# sticky-watch-v1_5.net
KiCad netlist of a schematic drawn in EAGLE
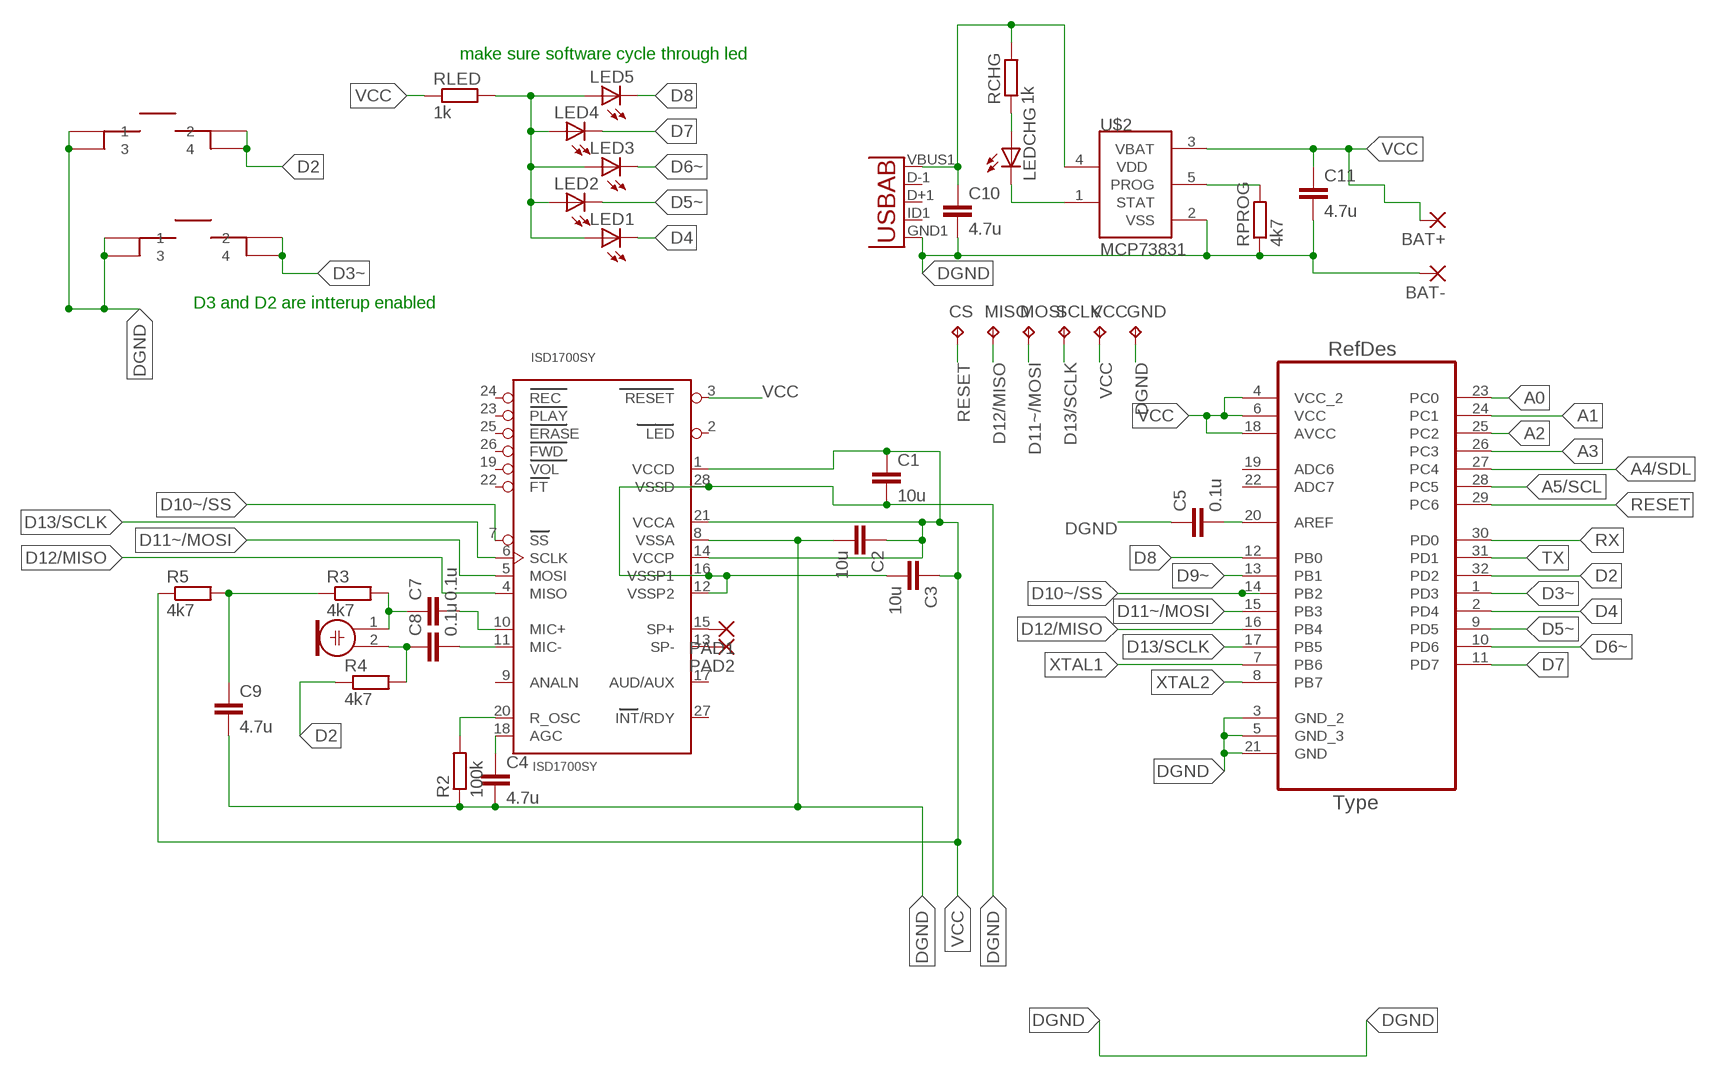
[diagram p0: schematic, sheet 1]

(export (version "E")
  (design (tool "Eeschema 10.0.6"))
  (components
    (comp (ref "BAT+")
      (value "1,6/0,8")
      (footprint "eagle-import:1,6_0,8")
      (libsource (lib "eagle-import") (part "1,6/0,8"))
    )
    (comp (ref "BAT-")
      (value "1,6/0,8")
      (footprint "eagle-import:1,6_0,8")
      (libsource (lib "eagle-import") (part "1,6/0,8"))
    )
    (comp (ref "C1")
      (value "10u")
      (footprint "eagle-import:C0603")
      (libsource (lib "eagle-import") (part "C-EUC0603"))
    )
    (comp (ref "C2")
      (value "10u")
      (footprint "eagle-import:C0603")
      (libsource (lib "eagle-import") (part "C-EUC0603"))
    )
    (comp (ref "C3")
      (value "10u")
      (footprint "eagle-import:C0603")
      (libsource (lib "eagle-import") (part "C-EUC0603"))
    )
    (comp (ref "C4")
      (value "4.7u")
      (footprint "eagle-import:C0603")
      (libsource (lib "eagle-import") (part "C-EUC0603"))
    )
    (comp (ref "C5")
      (value "0.1u")
      (footprint "eagle-import:C0603")
      (libsource (lib "eagle-import") (part "C-EUC0603"))
    )
    (comp (ref "C7")
      (value "0.1u")
      (footprint "eagle-import:C0603")
      (libsource (lib "eagle-import") (part "C-EUC0603"))
    )
    (comp (ref "C8")
      (value "0.1u")
      (footprint "eagle-import:C0603")
      (libsource (lib "eagle-import") (part "C-EUC0603"))
    )
    (comp (ref "C9")
      (value "4.7u")
      (footprint "eagle-import:C0603")
      (libsource (lib "eagle-import") (part "C-EUC0603"))
    )
    (comp (ref "C10")
      (value "4.7u")
      (footprint "eagle-import:C0603")
      (libsource (lib "eagle-import") (part "C-EUC0603"))
    )
    (comp (ref "C11")
      (value "4.7u")
      (footprint "eagle-import:C0603")
      (libsource (lib "eagle-import") (part "C-EUC0603"))
    )
    (comp (ref "CS")
      (value "TPTP10R")
      (footprint "eagle-import:TP10R")
      (libsource (lib "eagle-import") (part "TPTP10R"))
    )
    (comp (ref "GND")
      (value "TPTP10R")
      (footprint "eagle-import:TP10R")
      (libsource (lib "eagle-import") (part "TPTP10R"))
    )
    (comp (ref "ISD1700SY")
      (value "ISD1700SY")
      (footprint "eagle-import:SO28W")
      (libsource (lib "eagle-import") (part "ISD1700SY"))
    )
    (comp (ref "LED1")
      (value "LEDSML0805")
      (footprint "eagle-import:SML0805")
      (libsource (lib "eagle-import") (part "LEDSML0805"))
    )
    (comp (ref "LED2")
      (value "LEDSML0805")
      (footprint "eagle-import:SML0805")
      (libsource (lib "eagle-import") (part "LEDSML0805"))
    )
    (comp (ref "LED3")
      (value "LEDSML0805")
      (footprint "eagle-import:SML0805")
      (libsource (lib "eagle-import") (part "LEDSML0805"))
    )
    (comp (ref "LED4")
      (value "LEDSML0805")
      (footprint "eagle-import:SML0805")
      (libsource (lib "eagle-import") (part "LEDSML0805"))
    )
    (comp (ref "LED5")
      (value "LEDSML0805")
      (footprint "eagle-import:SML0805")
      (libsource (lib "eagle-import") (part "LEDSML0805"))
    )
    (comp (ref "LEDCHG")
      (value "LEDSML0805")
      (footprint "eagle-import:SML0805")
      (libsource (lib "eagle-import") (part "LEDSML0805"))
    )
    (comp (ref "M1")
      (value "ELECTRET_MICROPHON-WM-63PR")
      (footprint "eagle-import:WM-63PR")
      (libsource (lib "eagle-import") (part "ELECTRET_MICROPHON-WM-63PR"))
    )
    (comp (ref "MISO")
      (value "TPTP10R")
      (footprint "eagle-import:TP10R")
      (libsource (lib "eagle-import") (part "TPTP10R"))
    )
    (comp (ref "MOSI")
      (value "TPTP10R")
      (footprint "eagle-import:TP10R")
      (libsource (lib "eagle-import") (part "TPTP10R"))
    )
    (comp (ref "PAD1")
      (value "1,6/0,8")
      (footprint "eagle-import:1,6_0,8")
      (libsource (lib "eagle-import") (part "1,6/0,8"))
    )
    (comp (ref "PAD2")
      (value "1,6/0,8")
      (footprint "eagle-import:1,6_0,8")
      (libsource (lib "eagle-import") (part "1,6/0,8"))
    )
    (comp (ref "R2")
      (value "100k")
      (footprint "eagle-import:R0603")
      (libsource (lib "eagle-import") (part "R-EU_R0603"))
    )
    (comp (ref "R3")
      (value "4k7")
      (footprint "eagle-import:R0603")
      (libsource (lib "eagle-import") (part "R-EU_R0603"))
    )
    (comp (ref "R4")
      (value "4k7")
      (footprint "eagle-import:R0603")
      (libsource (lib "eagle-import") (part "R-EU_R0603"))
    )
    (comp (ref "R5")
      (value "4k7")
      (footprint "eagle-import:R0603")
      (libsource (lib "eagle-import") (part "R-EU_R0603"))
    )
    (comp (ref "RCHG")
      (value "1k")
      (footprint "eagle-import:R0603")
      (libsource (lib "eagle-import") (part "R-EU_R0603"))
    )
    (comp (ref "RLED")
      (value "1k")
      (footprint "eagle-import:R0603")
      (libsource (lib "eagle-import") (part "R-EU_R0603"))
    )
    (comp (ref "RPROG")
      (value "4k7")
      (footprint "eagle-import:R0603")
      (libsource (lib "eagle-import") (part "R-EU_R0603"))
    )
    (comp (ref "S1")
      (value "0")
      (footprint "eagle-import:SMD-TACT-5.2MM")
      (libsource (lib "eagle-import") (part "SMD-TACT"))
    )
    (comp (ref "S2")
      (value "SMD-TACT")
      (footprint "eagle-import:SMD-TACT-5.2MM")
      (libsource (lib "eagle-import") (part "SMD-TACT"))
    )
    (comp (ref "SCLK")
      (value "TPTP10R")
      (footprint "eagle-import:TP10R")
      (libsource (lib "eagle-import") (part "TPTP10R"))
    )
    (comp (ref "U$2")
      (value "MCP73831")
      (footprint "eagle-import:SOT23-5L")
      (libsource (lib "eagle-import") (part "MCP73831"))
    )
    (comp (ref "U1")
      (value "ATMEGA328P-AU")
      (footprint "eagle-import:QFP80P900X900X120-32N")
      (libsource (lib "eagle-import") (part "ATMEGA328P-AU"))
    )
    (comp (ref "U2")
      (value "USB\"\"")
      (footprint "eagle-import:USB-MICRO-SMD")
      (libsource (lib "eagle-import") (part "USB{dblquote}{dblquote}"))
    )
    (comp (ref "VCC")
      (value "TPTP10R")
      (footprint "eagle-import:TP10R")
      (libsource (lib "eagle-import") (part "TPTP10R"))
    )
  )
  (nets
    (net (code "1") (name "/D3~{}") (class "Default")
      (node (ref "S1") (pin "2") (pinfunction "2_2") (pintype "bidirectional"))
      (node (ref "S1") (pin "4") (pinfunction "4_4") (pintype "bidirectional"))
      (node (ref "U1") (pin "1") (pinfunction "PD3_1") (pintype "bidirectional"))
    )
    (net (code "2") (name "/D5~{}") (class "Default")
      (node (ref "LED2") (pin "C") (pinfunction "C_C") (pintype "passive"))
      (node (ref "U1") (pin "9") (pinfunction "PD5_9") (pintype "bidirectional"))
    )
    (net (code "3") (name "/D6~{}") (class "Default")
      (node (ref "LED3") (pin "C") (pinfunction "C_C") (pintype "passive"))
      (node (ref "U1") (pin "10") (pinfunction "PD6_10") (pintype "bidirectional"))
    )
    (net (code "4") (name "/D9~{}") (class "Default")
      (node (ref "U1") (pin "13") (pinfunction "PB1_13") (pintype "bidirectional"))
    )
    (net (code "5") (name "/D10~{{slash}SS}") (class "Default")
      (node (ref "ISD1700SY") (pin "7") (pinfunction "SS_7") (pintype "input"))
      (node (ref "U1") (pin "14") (pinfunction "PB2_14") (pintype "bidirectional"))
    )
    (net (code "6") (name "/D11~{{slash}MOSI}") (class "Default")
      (node (ref "ISD1700SY") (pin "5") (pinfunction "MOSI_5") (pintype "input"))
      (node (ref "MOSI") (pin "TP") (pinfunction "TP_TP") (pintype "input"))
      (node (ref "U1") (pin "15") (pinfunction "PB3_15") (pintype "bidirectional"))
    )
    (net (code "7") (name "A0") (class "Default")
      (node (ref "U1") (pin "23") (pinfunction "PC0_23") (pintype "bidirectional"))
    )
    (net (code "8") (name "A1") (class "Default")
      (node (ref "U1") (pin "24") (pinfunction "PC1_24") (pintype "bidirectional"))
    )
    (net (code "9") (name "A2") (class "Default")
      (node (ref "U1") (pin "25") (pinfunction "PC2_25") (pintype "bidirectional"))
    )
    (net (code "10") (name "A3") (class "Default")
      (node (ref "U1") (pin "26") (pinfunction "PC3_26") (pintype "bidirectional"))
    )
    (net (code "11") (name "A4{slash}SDL") (class "Default")
      (node (ref "U1") (pin "27") (pinfunction "PC4_27") (pintype "bidirectional"))
    )
    (net (code "12") (name "A5{slash}SCL") (class "Default")
      (node (ref "U1") (pin "28") (pinfunction "PC5_28") (pintype "bidirectional"))
    )
    (net (code "13") (name "D2") (class "Default")
      (node (ref "R4") (pin "1") (pinfunction "1_1") (pintype "passive"))
      (node (ref "S2") (pin "2") (pinfunction "2_2") (pintype "bidirectional"))
      (node (ref "S2") (pin "4") (pinfunction "4_4") (pintype "bidirectional"))
      (node (ref "U1") (pin "32") (pinfunction "PD2_32") (pintype "bidirectional"))
    )
    (net (code "14") (name "D4") (class "Default")
      (node (ref "LED1") (pin "C") (pinfunction "C_C") (pintype "passive"))
      (node (ref "U1") (pin "2") (pinfunction "PD4_2") (pintype "bidirectional"))
    )
    (net (code "15") (name "D7") (class "Default")
      (node (ref "LED4") (pin "C") (pinfunction "C_C") (pintype "passive"))
      (node (ref "U1") (pin "11") (pinfunction "PD7_11") (pintype "bidirectional"))
    )
    (net (code "16") (name "D8") (class "Default")
      (node (ref "LED5") (pin "C") (pinfunction "C_C") (pintype "passive"))
      (node (ref "U1") (pin "12") (pinfunction "PB0_12") (pintype "bidirectional"))
    )
    (net (code "17") (name "D12{slash}MISO") (class "Default")
      (node (ref "ISD1700SY") (pin "4") (pinfunction "MISO_4") (pintype "input"))
      (node (ref "MISO") (pin "TP") (pinfunction "TP_TP") (pintype "input"))
      (node (ref "U1") (pin "16") (pinfunction "PB4_16") (pintype "bidirectional"))
    )
    (net (code "18") (name "D13{slash}SCLK") (class "Default")
      (node (ref "ISD1700SY") (pin "6") (pinfunction "SCLK_6") (pintype "input"))
      (node (ref "SCLK") (pin "TP") (pinfunction "TP_TP") (pintype "input"))
      (node (ref "U1") (pin "17") (pinfunction "PB5_17") (pintype "bidirectional"))
    )
    (net (code "19") (name "DGND") (class "Default")
      (node (ref "BAT-") (pin "1") (pinfunction "P_1") (pintype "passive"))
      (node (ref "C1") (pin "2") (pinfunction "2_2") (pintype "passive"))
      (node (ref "C10") (pin "2") (pinfunction "2_2") (pintype "passive"))
      (node (ref "C11") (pin "2") (pinfunction "2_2") (pintype "passive"))
      (node (ref "C2") (pin "2") (pinfunction "2_2") (pintype "passive"))
      (node (ref "C3") (pin "2") (pinfunction "2_2") (pintype "passive"))
      (node (ref "C4") (pin "2") (pinfunction "2_2") (pintype "passive"))
      (node (ref "C5") (pin "1") (pinfunction "1_1") (pintype "passive"))
      (node (ref "C9") (pin "2") (pinfunction "2_2") (pintype "passive"))
      (node (ref "GND") (pin "TP") (pinfunction "TP_TP") (pintype "input"))
      (node (ref "ISD1700SY") (pin "12") (pinfunction "VSSP2_12") (pintype "power_in"))
      (node (ref "ISD1700SY") (pin "16") (pinfunction "VSSP1_16") (pintype "power_in"))
      (node (ref "ISD1700SY") (pin "28") (pinfunction "VSSD_28") (pintype "power_in"))
      (node (ref "ISD1700SY") (pin "8") (pinfunction "VSSA_8") (pintype "power_in"))
      (node (ref "R2") (pin "1") (pinfunction "1_1") (pintype "passive"))
      (node (ref "RPROG") (pin "1") (pinfunction "1_1") (pintype "passive"))
      (node (ref "S1") (pin "1") (pinfunction "1_1") (pintype "bidirectional"))
      (node (ref "S1") (pin "3") (pinfunction "3_3") (pintype "bidirectional"))
      (node (ref "S2") (pin "1") (pinfunction "1_1") (pintype "bidirectional"))
      (node (ref "S2") (pin "3") (pinfunction "3_3") (pintype "bidirectional"))
      (node (ref "U$2") (pin "2") (pinfunction "VSS_2") (pintype "bidirectional"))
      (node (ref "U1") (pin "21") (pinfunction "GND_21") (pintype "passive"))
      (node (ref "U1") (pin "3") (pinfunction "GND_2_3") (pintype "passive"))
      (node (ref "U1") (pin "5") (pinfunction "GND_3_5") (pintype "passive"))
      (node (ref "U2") (pin "GND1") (pinfunction "GND_GND1") (pintype "bidirectional"))
    )
    (net (code "20") (name "Net-(C7-Pad1)") (class "Default")
      (node (ref "C7") (pin "1") (pinfunction "1_1") (pintype "passive"))
      (node (ref "M1") (pin "1") (pinfunction "1_1") (pintype "passive"))
      (node (ref "R3") (pin "2") (pinfunction "2_2") (pintype "passive"))
    )
    (net (code "21") (name "Net-(C8-Pad1)") (class "Default")
      (node (ref "C8") (pin "1") (pinfunction "1_1") (pintype "passive"))
      (node (ref "M1") (pin "2") (pinfunction "2_2") (pintype "passive"))
      (node (ref "R4") (pin "2") (pinfunction "2_2") (pintype "passive"))
    )
    (net (code "22") (name "Net-(C9-Pad1)") (class "Default")
      (node (ref "C9") (pin "1") (pinfunction "1_1") (pintype "passive"))
      (node (ref "R3") (pin "1") (pinfunction "1_1") (pintype "passive"))
      (node (ref "R5") (pin "2") (pinfunction "2_2") (pintype "passive"))
    )
    (net (code "23") (name "Net-(ISD1700SY-AGC)") (class "Default")
      (node (ref "C4") (pin "1") (pinfunction "1_1") (pintype "passive"))
      (node (ref "ISD1700SY") (pin "18") (pinfunction "AGC_18") (pintype "passive"))
    )
    (net (code "24") (name "Net-(ISD1700SY-MIC+)") (class "Default")
      (node (ref "C7") (pin "2") (pinfunction "2_2") (pintype "passive"))
      (node (ref "ISD1700SY") (pin "10") (pinfunction "MIC+_10") (pintype "input"))
    )
    (net (code "25") (name "Net-(ISD1700SY-MIC-)") (class "Default")
      (node (ref "C8") (pin "2") (pinfunction "2_2") (pintype "passive"))
      (node (ref "ISD1700SY") (pin "11") (pinfunction "MIC-_11") (pintype "input"))
    )
    (net (code "26") (name "Net-(ISD1700SY-R_OSC)") (class "Default")
      (node (ref "ISD1700SY") (pin "20") (pinfunction "R_OSC_20") (pintype "passive"))
      (node (ref "R2") (pin "2") (pinfunction "2_2") (pintype "passive"))
    )
    (net (code "27") (name "Net-(ISD1700SY-SP+)") (class "Default")
      (node (ref "ISD1700SY") (pin "15") (pinfunction "SP+_15") (pintype "output"))
      (node (ref "PAD1") (pin "1") (pinfunction "P_1") (pintype "passive"))
    )
    (net (code "28") (name "Net-(ISD1700SY-SP-)") (class "Default")
      (node (ref "ISD1700SY") (pin "13") (pinfunction "SP-_13") (pintype "output"))
      (node (ref "PAD2") (pin "1") (pinfunction "P_1") (pintype "passive"))
    )
    (net (code "29") (name "Net-(LED1-PadA)") (class "Default")
      (node (ref "LED1") (pin "A") (pinfunction "A_A") (pintype "passive"))
      (node (ref "LED2") (pin "A") (pinfunction "A_A") (pintype "passive"))
      (node (ref "LED3") (pin "A") (pinfunction "A_A") (pintype "passive"))
      (node (ref "LED4") (pin "A") (pinfunction "A_A") (pintype "passive"))
      (node (ref "LED5") (pin "A") (pinfunction "A_A") (pintype "passive"))
      (node (ref "RLED") (pin "2") (pinfunction "2_2") (pintype "passive"))
    )
    (net (code "30") (name "Net-(LEDCHG-PadA)") (class "Default")
      (node (ref "LEDCHG") (pin "A") (pinfunction "A_A") (pintype "passive"))
      (node (ref "RCHG") (pin "1") (pinfunction "1_1") (pintype "passive"))
    )
    (net (code "31") (name "Net-(U$2-PROG)") (class "Default")
      (node (ref "RPROG") (pin "2") (pinfunction "2_2") (pintype "passive"))
      (node (ref "U$2") (pin "5") (pinfunction "PROG_5") (pintype "bidirectional"))
    )
    (net (code "32") (name "Net-(U$2-STAT)") (class "Default")
      (node (ref "LEDCHG") (pin "C") (pinfunction "C_C") (pintype "passive"))
      (node (ref "U$2") (pin "1") (pinfunction "STAT_1") (pintype "bidirectional"))
    )
    (net (code "33") (name "Net-(U$2-VDD)") (class "Default")
      (node (ref "C10") (pin "1") (pinfunction "1_1") (pintype "passive"))
      (node (ref "RCHG") (pin "2") (pinfunction "2_2") (pintype "passive"))
      (node (ref "U$2") (pin "4") (pinfunction "VDD_4") (pintype "bidirectional"))
      (node (ref "U2") (pin "VBUS1") (pinfunction "VBUS_VBUS1") (pintype "bidirectional"))
    )
    (net (code "34") (name "Net-(U1-AREF)") (class "Default")
      (node (ref "C5") (pin "2") (pinfunction "2_2") (pintype "passive"))
      (node (ref "U1") (pin "20") (pinfunction "AREF_20") (pintype "input"))
    )
    (net (code "35") (name "RESET") (class "Default")
      (node (ref "CS") (pin "TP") (pinfunction "TP_TP") (pintype "input"))
      (node (ref "U1") (pin "29") (pinfunction "PC6_29") (pintype "bidirectional"))
    )
    (net (code "36") (name "RX") (class "Default")
      (node (ref "U1") (pin "30") (pinfunction "PD0_30") (pintype "bidirectional"))
    )
    (net (code "37") (name "TX") (class "Default")
      (node (ref "U1") (pin "31") (pinfunction "PD1_31") (pintype "bidirectional"))
    )
    (net (code "38") (name "VCC") (class "Default")
      (node (ref "BAT+") (pin "1") (pinfunction "P_1") (pintype "passive"))
      (node (ref "C1") (pin "1") (pinfunction "1_1") (pintype "passive"))
      (node (ref "C11") (pin "1") (pinfunction "1_1") (pintype "passive"))
      (node (ref "C2") (pin "1") (pinfunction "1_1") (pintype "passive"))
      (node (ref "C3") (pin "1") (pinfunction "1_1") (pintype "passive"))
      (node (ref "ISD1700SY") (pin "1") (pinfunction "VCCD_1") (pintype "power_in"))
      (node (ref "ISD1700SY") (pin "14") (pinfunction "VCCP_14") (pintype "power_in"))
      (node (ref "ISD1700SY") (pin "21") (pinfunction "VCCA_21") (pintype "power_in"))
      (node (ref "ISD1700SY") (pin "3") (pinfunction "RESET_3") (pintype "input"))
      (node (ref "R5") (pin "1") (pinfunction "1_1") (pintype "passive"))
      (node (ref "RLED") (pin "1") (pinfunction "1_1") (pintype "passive"))
      (node (ref "U$2") (pin "3") (pinfunction "VBAT_3") (pintype "bidirectional"))
      (node (ref "U1") (pin "18") (pinfunction "AVCC_18") (pintype "power_in"))
      (node (ref "U1") (pin "4") (pinfunction "VCC_2_4") (pintype "power_in"))
      (node (ref "U1") (pin "6") (pinfunction "VCC_6") (pintype "power_in"))
      (node (ref "VCC") (pin "TP") (pinfunction "TP_TP") (pintype "input"))
    )
    (net (code "39") (name "XTAL1") (class "Default")
      (node (ref "U1") (pin "7") (pinfunction "PB6_7") (pintype "bidirectional"))
    )
    (net (code "40") (name "XTAL2") (class "Default")
      (node (ref "U1") (pin "8") (pinfunction "PB7_8") (pintype "bidirectional"))
    )
    (net (code "41") (name "unconnected-(ISD1700SY-ANALN-Pad9)") (class "Default")
      (node (ref "ISD1700SY") (pin "9") (pinfunction "ANALN_9") (pintype "input"))
    )
    (net (code "42") (name "unconnected-(ISD1700SY-AUD{slash}AUX-Pad17)") (class "Default")
      (node (ref "ISD1700SY") (pin "17") (pinfunction "AUD/AUX_17") (pintype "output"))
    )
    (net (code "43") (name "unconnected-(ISD1700SY-ERASE-Pad25)") (class "Default")
      (node (ref "ISD1700SY") (pin "25") (pinfunction "ERASE_25") (pintype "input"))
    )
    (net (code "44") (name "unconnected-(ISD1700SY-FT-Pad22)") (class "Default")
      (node (ref "ISD1700SY") (pin "22") (pinfunction "FT_22") (pintype "input"))
    )
    (net (code "45") (name "unconnected-(ISD1700SY-FWD-Pad26)") (class "Default")
      (node (ref "ISD1700SY") (pin "26") (pinfunction "FWD_26") (pintype "input"))
    )
    (net (code "46") (name "unconnected-(ISD1700SY-INT{slash}RDY-Pad27)") (class "Default")
      (node (ref "ISD1700SY") (pin "27") (pinfunction "INT/RDY_27") (pintype "bidirectional"))
    )
    (net (code "47") (name "unconnected-(ISD1700SY-LED-Pad2)") (class "Default")
      (node (ref "ISD1700SY") (pin "2") (pinfunction "LED_2") (pintype "input"))
    )
    (net (code "48") (name "unconnected-(ISD1700SY-PLAY-Pad23)") (class "Default")
      (node (ref "ISD1700SY") (pin "23") (pinfunction "PLAY_23") (pintype "input"))
    )
    (net (code "49") (name "unconnected-(ISD1700SY-REC-Pad24)") (class "Default")
      (node (ref "ISD1700SY") (pin "24") (pinfunction "REC_24") (pintype "input"))
    )
    (net (code "50") (name "unconnected-(ISD1700SY-VOL-Pad19)") (class "Default")
      (node (ref "ISD1700SY") (pin "19") (pinfunction "VOL_19") (pintype "input"))
    )
    (net (code "51") (name "unconnected-(U1-ADC6-Pad19)") (class "Default")
      (node (ref "U1") (pin "19") (pinfunction "ADC6_19") (pintype "input"))
    )
    (net (code "52") (name "unconnected-(U1-ADC7-Pad22)") (class "Default")
      (node (ref "U1") (pin "22") (pinfunction "ADC7_22") (pintype "input"))
    )
    (net (code "53") (name "unconnected-(U2-D+-PadD+1)") (class "Default")
      (node (ref "U2") (pin "D+1") (pinfunction "D+_D+1") (pintype "bidirectional"))
    )
    (net (code "54") (name "unconnected-(U2-D--PadD-1)") (class "Default")
      (node (ref "U2") (pin "D-1") (pinfunction "D-_D-1") (pintype "bidirectional"))
    )
    (net (code "55") (name "unconnected-(U2-USBID-PadID1)") (class "Default")
      (node (ref "U2") (pin "ID1") (pinfunction "USBID_ID1") (pintype "bidirectional"))
    )
  )
)
